# wireless-display-design.net
KiCad netlist of a schematic drawn in EasyEDA Pro
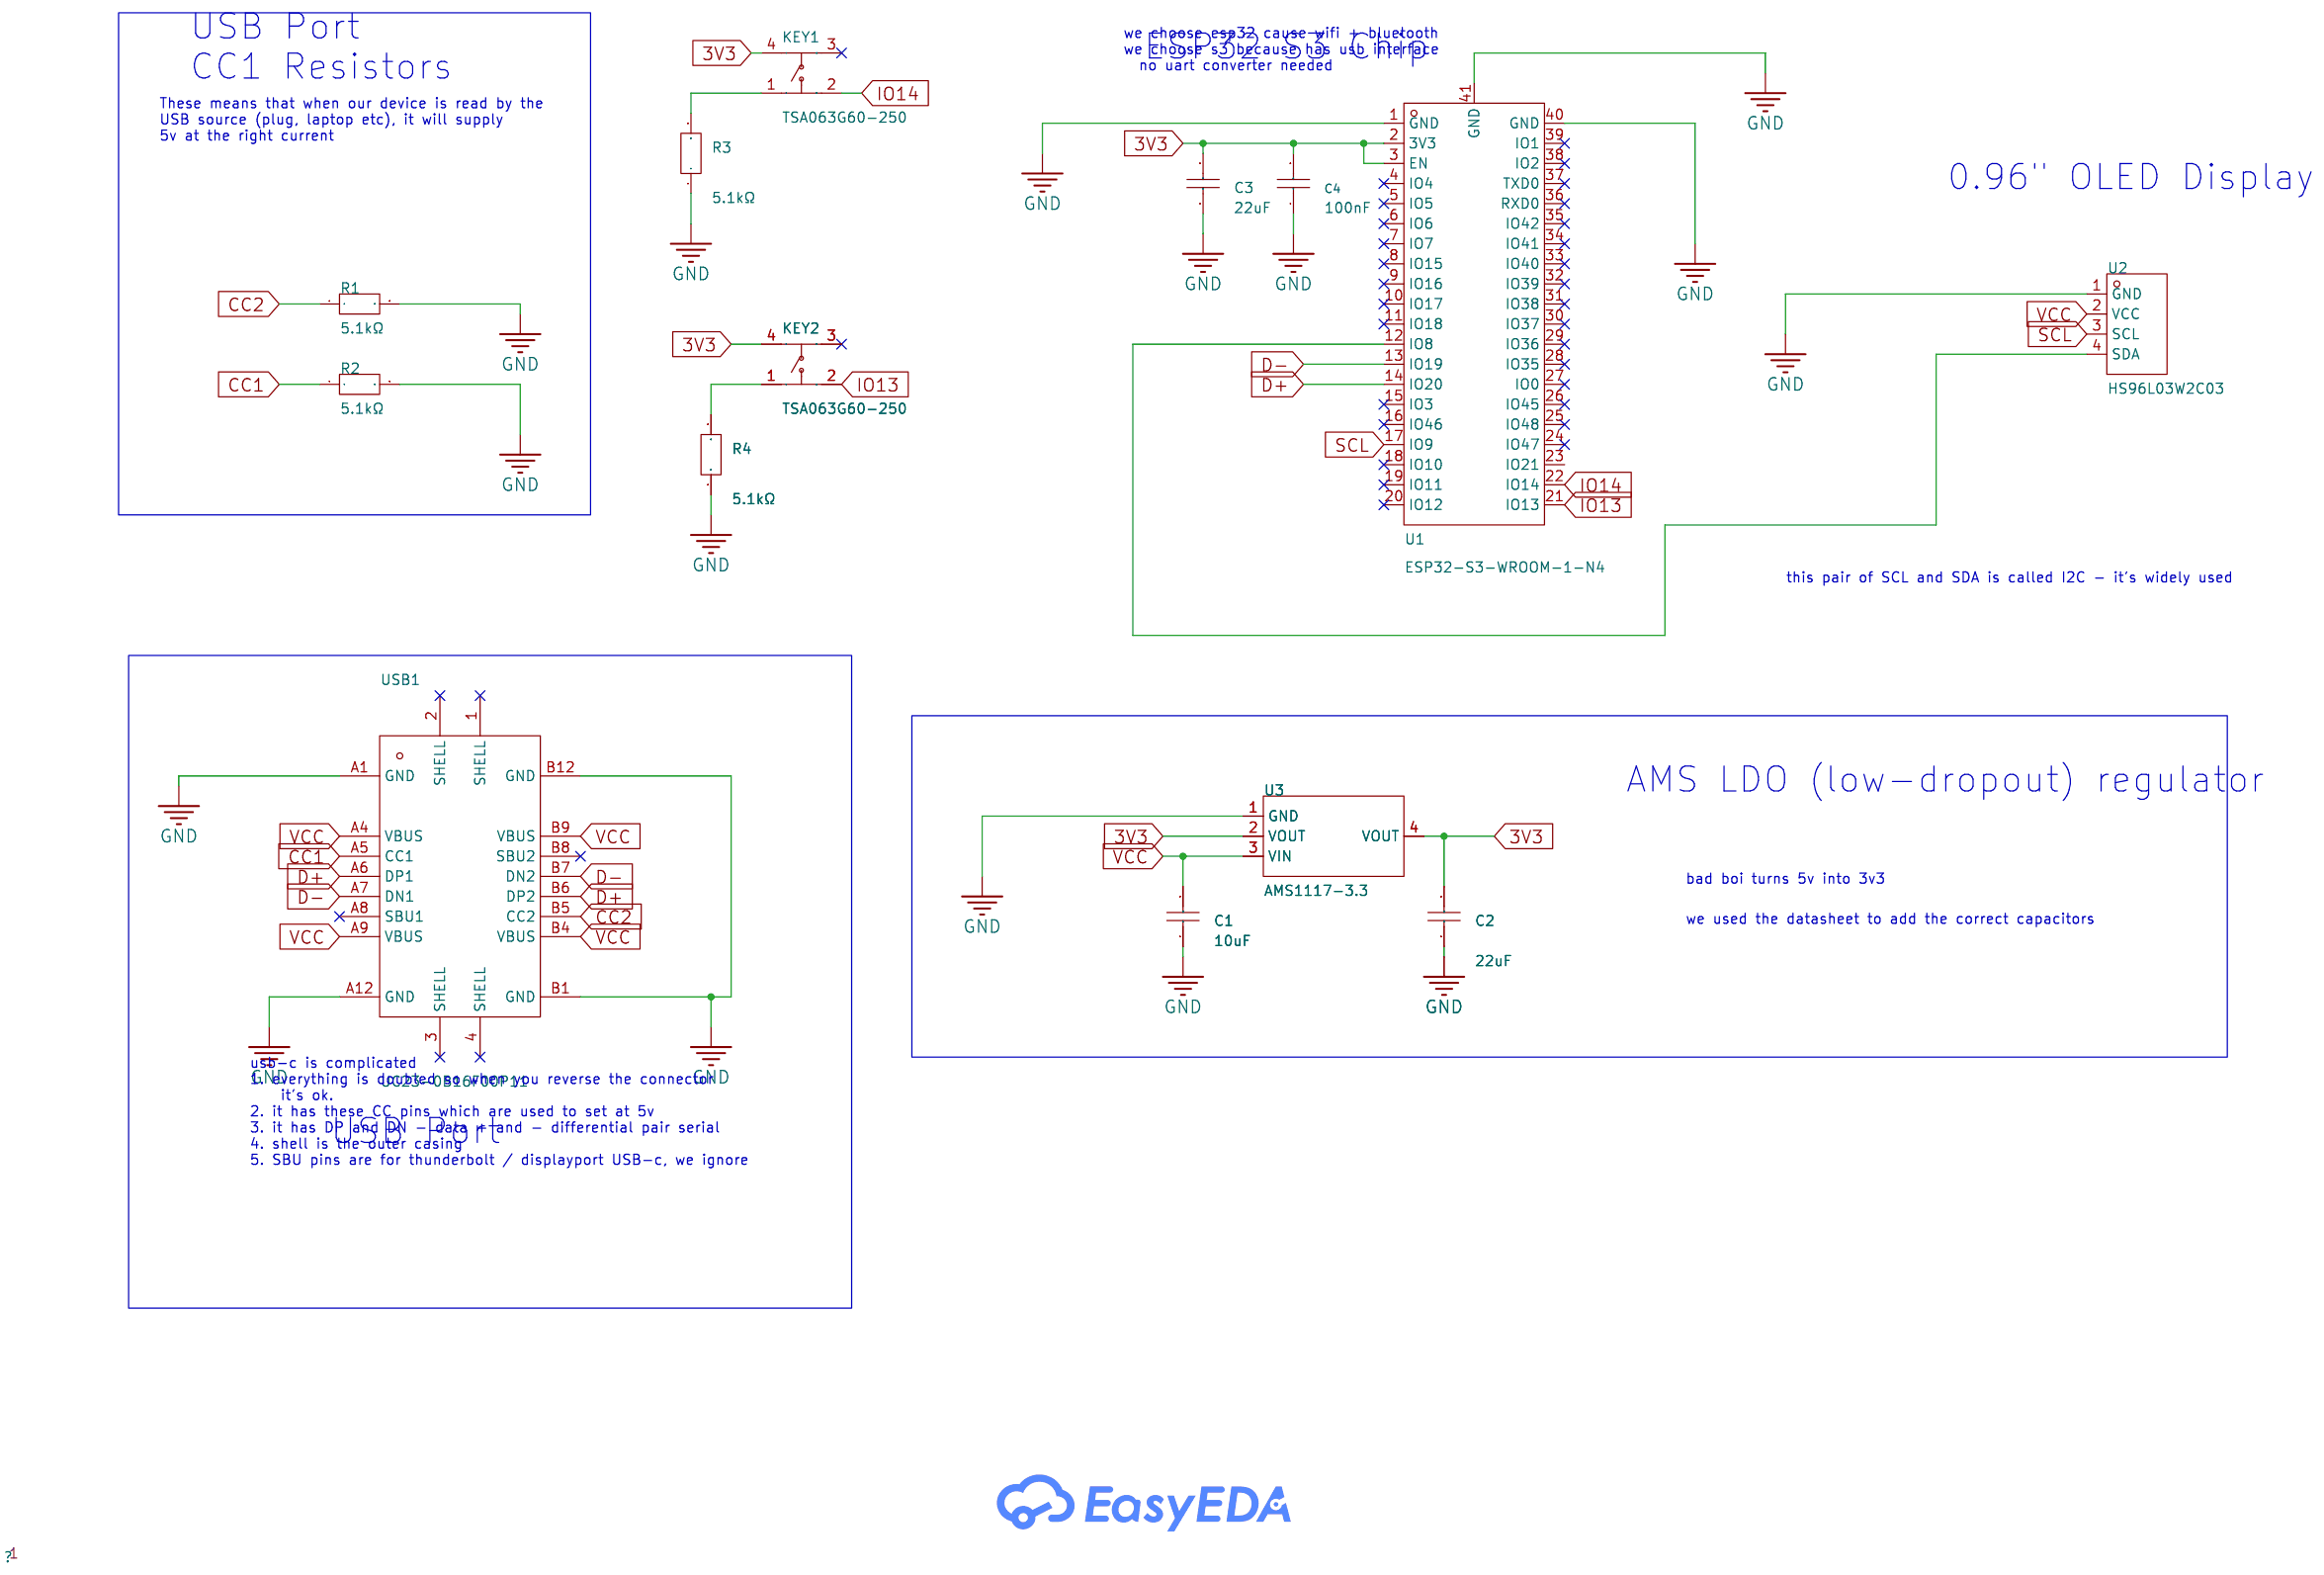
[diagram p0: schematic sheet]

(export (version "E")
  (design (tool "Eeschema 10.0.6"))
  (components
    (comp (ref "C1")
      (value "10uF")
      (footprint "easyedapro:C1206")
      (description "Capacitance:10uF Tolerance:±10% Tolerance:±10% Voltage Rating:50V Temperature Coefficient:X5R")
      (fields
        (field (name "Manufacturer Part") "CL31A106KBHNNNE")
        (field (name "Manufacturer") "SAMSUNG(三星)")
      )
      (libsource (lib "easyedapro") (part "CL31A106KBHNNNE"))
    )
    (comp (ref "C2")
      (value "22uF")
      (footprint "easyedapro:C1206")
      (description "Capacitance:22uF Tolerance:±10% Tolerance:±10% Voltage Rating:25V Temperature Coefficient:X5R")
      (fields
        (field (name "Manufacturer Part") "CL31A226KAHNNNE")
        (field (name "Manufacturer") "SAMSUNG(三星)")
      )
      (libsource (lib "easyedapro") (part "CL31A226KAHNNNE"))
    )
    (comp (ref "C3")
      (value "22uF")
      (footprint "easyedapro:C1206")
      (description "Capacitance:22uF Tolerance:±10% Tolerance:±10% Voltage Rating:25V Temperature Coefficient:X5R")
      (fields
        (field (name "Manufacturer Part") "CL31A226KAHNNNE")
        (field (name "Manufacturer") "SAMSUNG(三星)")
      )
      (libsource (lib "easyedapro") (part "CL31A226KAHNNNE"))
    )
    (comp (ref "C4")
      (value "100nF")
      (footprint "easyedapro:C1206")
      (description "Capacitance:100nF Tolerance:±10% Tolerance:±10% Voltage Rating:50V Temperature Coefficient:X7R")
      (fields
        (field (name "Manufacturer Part") "CL31B104KBCNNNC")
        (field (name "Manufacturer") "SAMSUNG(三星)")
      )
      (libsource (lib "easyedapro") (part "CL31B104KBCNNNC"))
    )
    (comp (ref "KEY1")
      (value "TSA063G60-250")
      (footprint "easyedapro:KEY-SMD_4P-L6.1-W6.1-P4.50-LS9.0")
      (fields (field (name "Manufacturer") "BRIGHT(博瑞泰)"))
      (libsource (lib "easyedapro") (part "TSA063G60-250"))
    )
    (comp (ref "KEY2")
      (value "TSA063G60-250")
      (footprint "easyedapro:KEY-SMD_4P-L6.1-W6.1-P4.50-LS9.0")
      (fields (field (name "Manufacturer") "BRIGHT(博瑞泰)"))
      (libsource (lib "easyedapro") (part "TSA063G60-250"))
    )
    (comp (ref "R1")
      (value "5.1kΩ")
      (footprint "easyedapro:R1206")
      (fields (field (name "Manufacturer Part") "FRC1206J512 TS") (field (name "Manufacturer") "FOJAN(富捷)"))
      (libsource (lib "easyedapro") (part "FRC1206J512 TS"))
    )
    (comp (ref "R2")
      (value "5.1kΩ")
      (footprint "easyedapro:R1206")
      (fields (field (name "Manufacturer Part") "FRC1206J512 TS") (field (name "Manufacturer") "FOJAN(富捷)"))
      (libsource (lib "easyedapro") (part "FRC1206J512 TS"))
    )
    (comp (ref "R3")
      (value "5.1kΩ")
      (footprint "easyedapro:R1206")
      (fields (field (name "Manufacturer Part") "FRC1206J512 TS") (field (name "Manufacturer") "FOJAN(富捷)"))
      (libsource (lib "easyedapro") (part "FRC1206J512 TS"))
    )
    (comp (ref "R4")
      (value "5.1kΩ")
      (footprint "easyedapro:R1206")
      (fields (field (name "Manufacturer Part") "FRC1206J512 TS") (field (name "Manufacturer") "FOJAN(富捷)"))
      (libsource (lib "easyedapro") (part "FRC1206J512 TS"))
    )
    (comp (ref "U1")
      (value "ESP32-S3-WROOM-1-N4")
      (footprint "easyedapro:WIFIM-SMD_ESP32-S3-WROOM-1-N8")
      (fields (field (name "Manufacturer") "ESPRESSIF(乐鑫)"))
      (libsource (lib "easyedapro") (part "ESP32-S3-WROOM-1-N4"))
    )
    (comp (ref "U2")
      (value "HS96L03W2C03")
      (footprint "easyedapro:OLED-TH_L27.8-W27.2-P2.54_C9900033791")
      (fields (field (name "Manufacturer") "HS(汉昇)"))
      (libsource (lib "easyedapro") (part "HS96L03W2C03"))
    )
    (comp (ref "U3")
      (value "AMS1117-3.3")
      (footprint "easyedapro:SOT-223-3_L6.5-W3.4-P2.30-LS7.0-BR")
      (fields (field (name "Manufacturer") "AMS"))
      (libsource (lib "easyedapro") (part "AMS1117-3.3"))
    )
    (comp (ref "USB1")
      (value "UC23-0B16F00P11")
      (footprint "easyedapro:USB-C-TH_UC23-0B16F00P11")
      (fields (field (name "Manufacturer") "BXCONN(宝讯)"))
      (libsource (lib "easyedapro") (part "UC23-0B16F00P11"))
    )
  )
  (nets
    (net (code "1") (name "3V3") (class "Default")
      (node (ref "C2") (pin "2") (pinfunction "2_2") (pintype "input"))
      (node (ref "C3") (pin "2") (pinfunction "2_2") (pintype "input"))
      (node (ref "C4") (pin "2") (pinfunction "2_2") (pintype "input"))
      (node (ref "KEY1") (pin "4") (pinfunction "4_4") (pintype "input"))
      (node (ref "KEY2") (pin "4") (pinfunction "4_4") (pintype "input"))
      (node (ref "U1") (pin "2") (pinfunction "3V3_2") (pintype "unspecified"))
      (node (ref "U1") (pin "3") (pinfunction "EN_3") (pintype "unspecified"))
      (node (ref "U3") (pin "2") (pinfunction "VOUT_2") (pintype "unspecified"))
      (node (ref "U3") (pin "4") (pinfunction "VOUT_4") (pintype "unspecified"))
    )
    (net (code "2") (name "CC1") (class "Default")
      (node (ref "R2") (pin "1") (pinfunction "1_1") (pintype "unspecified"))
      (node (ref "USB1") (pin "A5") (pinfunction "CC1_A5") (pintype "unspecified"))
    )
    (net (code "3") (name "CC2") (class "Default")
      (node (ref "R1") (pin "1") (pinfunction "1_1") (pintype "unspecified"))
      (node (ref "USB1") (pin "B5") (pinfunction "CC2_B5") (pintype "unspecified"))
    )
    (net (code "4") (name "D+") (class "Default")
      (node (ref "U1") (pin "14") (pinfunction "IO20_14") (pintype "unspecified"))
      (node (ref "USB1") (pin "A6") (pinfunction "DP1_A6") (pintype "unspecified"))
      (node (ref "USB1") (pin "B6") (pinfunction "DP2_B6") (pintype "unspecified"))
    )
    (net (code "5") (name "D-") (class "Default")
      (node (ref "U1") (pin "13") (pinfunction "IO19_13") (pintype "unspecified"))
      (node (ref "USB1") (pin "A7") (pinfunction "DN1_A7") (pintype "unspecified"))
      (node (ref "USB1") (pin "B7") (pinfunction "DN2_B7") (pintype "unspecified"))
    )
    (net (code "6") (name "GND") (class "Default")
      (node (ref "C1") (pin "1") (pinfunction "1_1") (pintype "input"))
      (node (ref "C2") (pin "1") (pinfunction "1_1") (pintype "input"))
      (node (ref "C3") (pin "1") (pinfunction "1_1") (pintype "input"))
      (node (ref "C4") (pin "1") (pinfunction "1_1") (pintype "input"))
      (node (ref "R1") (pin "2") (pinfunction "2_2") (pintype "unspecified"))
      (node (ref "R2") (pin "2") (pinfunction "2_2") (pintype "unspecified"))
      (node (ref "R3") (pin "1") (pinfunction "1_1") (pintype "unspecified"))
      (node (ref "R4") (pin "1") (pinfunction "1_1") (pintype "unspecified"))
      (node (ref "U1") (pin "1") (pinfunction "GND_1") (pintype "unspecified"))
      (node (ref "U1") (pin "40") (pinfunction "GND_40") (pintype "unspecified"))
      (node (ref "U1") (pin "41") (pinfunction "GND_41") (pintype "unspecified"))
      (node (ref "U2") (pin "1") (pinfunction "GND_1") (pintype "unspecified"))
      (node (ref "U3") (pin "1") (pinfunction "GND_1") (pintype "unspecified"))
      (node (ref "USB1") (pin "A1") (pinfunction "GND_A1") (pintype "unspecified"))
      (node (ref "USB1") (pin "A12") (pinfunction "GND_A12") (pintype "unspecified"))
      (node (ref "USB1") (pin "B1") (pinfunction "GND_B1") (pintype "unspecified"))
      (node (ref "USB1") (pin "B12") (pinfunction "GND_B12") (pintype "unspecified"))
    )
    (net (code "7") (name "IO13") (class "Default")
      (node (ref "KEY2") (pin "2") (pinfunction "2_2") (pintype "input"))
      (node (ref "U1") (pin "21") (pinfunction "IO13_21") (pintype "unspecified"))
    )
    (net (code "8") (name "IO14") (class "Default")
      (node (ref "KEY1") (pin "2") (pinfunction "2_2") (pintype "input"))
      (node (ref "U1") (pin "22") (pinfunction "IO14_22") (pintype "unspecified"))
    )
    (net (code "9") (name "Net-(KEY1-Pad1)") (class "Default")
      (node (ref "KEY1") (pin "1") (pinfunction "1_1") (pintype "input"))
      (node (ref "R3") (pin "2") (pinfunction "2_2") (pintype "unspecified"))
    )
    (net (code "10") (name "Net-(KEY2-Pad1)") (class "Default")
      (node (ref "KEY2") (pin "1") (pinfunction "1_1") (pintype "input"))
      (node (ref "R4") (pin "2") (pinfunction "2_2") (pintype "unspecified"))
    )
    (net (code "11") (name "Net-(U1-IO8)") (class "Default")
      (node (ref "U1") (pin "12") (pinfunction "IO8_12") (pintype "unspecified"))
      (node (ref "U2") (pin "4") (pinfunction "SDA_4") (pintype "unspecified"))
    )
    (net (code "12") (name "SCL") (class "Default")
      (node (ref "U1") (pin "17") (pinfunction "IO9_17") (pintype "unspecified"))
      (node (ref "U2") (pin "3") (pinfunction "SCL_3") (pintype "unspecified"))
    )
    (net (code "13") (name "VCC") (class "Default")
      (node (ref "C1") (pin "2") (pinfunction "2_2") (pintype "input"))
      (node (ref "U2") (pin "2") (pinfunction "VCC_2") (pintype "unspecified"))
      (node (ref "U3") (pin "3") (pinfunction "VIN_3") (pintype "unspecified"))
      (node (ref "USB1") (pin "A4") (pinfunction "VBUS_A4") (pintype "unspecified"))
      (node (ref "USB1") (pin "A9") (pinfunction "VBUS_A9") (pintype "unspecified"))
      (node (ref "USB1") (pin "B4") (pinfunction "VBUS_B4") (pintype "unspecified"))
      (node (ref "USB1") (pin "B9") (pinfunction "VBUS_B9") (pintype "unspecified"))
    )
    (net (code "14") (name "unconnected-(KEY1-Pad3)") (class "Default")
      (node (ref "KEY1") (pin "3") (pinfunction "3_3") (pintype "input+no_connect"))
    )
    (net (code "15") (name "unconnected-(KEY2-Pad3)") (class "Default")
      (node (ref "KEY2") (pin "3") (pinfunction "3_3") (pintype "input+no_connect"))
    )
    (net (code "16") (name "unconnected-(U1-IO0-Pad27)") (class "Default")
      (node (ref "U1") (pin "27") (pinfunction "IO0_27") (pintype "unspecified+no_connect"))
    )
    (net (code "17") (name "unconnected-(U1-IO1-Pad39)") (class "Default")
      (node (ref "U1") (pin "39") (pinfunction "IO1_39") (pintype "unspecified+no_connect"))
    )
    (net (code "18") (name "unconnected-(U1-IO2-Pad38)") (class "Default")
      (node (ref "U1") (pin "38") (pinfunction "IO2_38") (pintype "unspecified+no_connect"))
    )
    (net (code "19") (name "unconnected-(U1-IO3-Pad15)") (class "Default")
      (node (ref "U1") (pin "15") (pinfunction "IO3_15") (pintype "unspecified+no_connect"))
    )
    (net (code "20") (name "unconnected-(U1-IO4-Pad4)") (class "Default")
      (node (ref "U1") (pin "4") (pinfunction "IO4_4") (pintype "unspecified+no_connect"))
    )
    (net (code "21") (name "unconnected-(U1-IO5-Pad5)") (class "Default")
      (node (ref "U1") (pin "5") (pinfunction "IO5_5") (pintype "unspecified+no_connect"))
    )
    (net (code "22") (name "unconnected-(U1-IO6-Pad6)") (class "Default")
      (node (ref "U1") (pin "6") (pinfunction "IO6_6") (pintype "unspecified+no_connect"))
    )
    (net (code "23") (name "unconnected-(U1-IO7-Pad7)") (class "Default")
      (node (ref "U1") (pin "7") (pinfunction "IO7_7") (pintype "unspecified+no_connect"))
    )
    (net (code "24") (name "unconnected-(U1-IO10-Pad18)") (class "Default")
      (node (ref "U1") (pin "18") (pinfunction "IO10_18") (pintype "unspecified+no_connect"))
    )
    (net (code "25") (name "unconnected-(U1-IO11-Pad19)") (class "Default")
      (node (ref "U1") (pin "19") (pinfunction "IO11_19") (pintype "unspecified+no_connect"))
    )
    (net (code "26") (name "unconnected-(U1-IO12-Pad20)") (class "Default")
      (node (ref "U1") (pin "20") (pinfunction "IO12_20") (pintype "unspecified+no_connect"))
    )
    (net (code "27") (name "unconnected-(U1-IO15-Pad8)") (class "Default")
      (node (ref "U1") (pin "8") (pinfunction "IO15_8") (pintype "unspecified+no_connect"))
    )
    (net (code "28") (name "unconnected-(U1-IO16-Pad9)") (class "Default")
      (node (ref "U1") (pin "9") (pinfunction "IO16_9") (pintype "unspecified+no_connect"))
    )
    (net (code "29") (name "unconnected-(U1-IO17-Pad10)") (class "Default")
      (node (ref "U1") (pin "10") (pinfunction "IO17_10") (pintype "unspecified+no_connect"))
    )
    (net (code "30") (name "unconnected-(U1-IO18-Pad11)") (class "Default")
      (node (ref "U1") (pin "11") (pinfunction "IO18_11") (pintype "unspecified+no_connect"))
    )
    (net (code "31") (name "unconnected-(U1-IO21-Pad23)") (class "Default")
      (node (ref "U1") (pin "23") (pinfunction "IO21_23") (pintype "unspecified"))
    )
    (net (code "32") (name "unconnected-(U1-IO35-Pad28)") (class "Default")
      (node (ref "U1") (pin "28") (pinfunction "IO35_28") (pintype "unspecified+no_connect"))
    )
    (net (code "33") (name "unconnected-(U1-IO36-Pad29)") (class "Default")
      (node (ref "U1") (pin "29") (pinfunction "IO36_29") (pintype "unspecified+no_connect"))
    )
    (net (code "34") (name "unconnected-(U1-IO37-Pad30)") (class "Default")
      (node (ref "U1") (pin "30") (pinfunction "IO37_30") (pintype "unspecified+no_connect"))
    )
    (net (code "35") (name "unconnected-(U1-IO38-Pad31)") (class "Default")
      (node (ref "U1") (pin "31") (pinfunction "IO38_31") (pintype "unspecified+no_connect"))
    )
    (net (code "36") (name "unconnected-(U1-IO39-Pad32)") (class "Default")
      (node (ref "U1") (pin "32") (pinfunction "IO39_32") (pintype "unspecified+no_connect"))
    )
    (net (code "37") (name "unconnected-(U1-IO40-Pad33)") (class "Default")
      (node (ref "U1") (pin "33") (pinfunction "IO40_33") (pintype "unspecified+no_connect"))
    )
    (net (code "38") (name "unconnected-(U1-IO41-Pad34)") (class "Default")
      (node (ref "U1") (pin "34") (pinfunction "IO41_34") (pintype "unspecified+no_connect"))
    )
    (net (code "39") (name "unconnected-(U1-IO42-Pad35)") (class "Default")
      (node (ref "U1") (pin "35") (pinfunction "IO42_35") (pintype "unspecified+no_connect"))
    )
    (net (code "40") (name "unconnected-(U1-IO45-Pad26)") (class "Default")
      (node (ref "U1") (pin "26") (pinfunction "IO45_26") (pintype "unspecified+no_connect"))
    )
    (net (code "41") (name "unconnected-(U1-IO46-Pad16)") (class "Default")
      (node (ref "U1") (pin "16") (pinfunction "IO46_16") (pintype "unspecified+no_connect"))
    )
    (net (code "42") (name "unconnected-(U1-IO47-Pad24)") (class "Default")
      (node (ref "U1") (pin "24") (pinfunction "IO47_24") (pintype "unspecified+no_connect"))
    )
    (net (code "43") (name "unconnected-(U1-IO48-Pad25)") (class "Default")
      (node (ref "U1") (pin "25") (pinfunction "IO48_25") (pintype "unspecified+no_connect"))
    )
    (net (code "44") (name "unconnected-(U1-RXD0-Pad36)") (class "Default")
      (node (ref "U1") (pin "36") (pinfunction "RXD0_36") (pintype "unspecified+no_connect"))
    )
    (net (code "45") (name "unconnected-(U1-TXD0-Pad37)") (class "Default")
      (node (ref "U1") (pin "37") (pinfunction "TXD0_37") (pintype "unspecified+no_connect"))
    )
    (net (code "46") (name "unconnected-(USB1-SBU1-PadA8)") (class "Default")
      (node (ref "USB1") (pin "A8") (pinfunction "SBU1_A8") (pintype "unspecified+no_connect"))
    )
    (net (code "47") (name "unconnected-(USB1-SBU2-PadB8)") (class "Default")
      (node (ref "USB1") (pin "B8") (pinfunction "SBU2_B8") (pintype "unspecified+no_connect"))
    )
    (net (code "48") (name "unconnected-(USB1-SHELL-Pad1)") (class "Default")
      (node (ref "USB1") (pin "1") (pinfunction "SHELL_1") (pintype "unspecified+no_connect"))
    )
    (net (code "49") (name "unconnected-(USB1-SHELL-Pad2)") (class "Default")
      (node (ref "USB1") (pin "2") (pinfunction "SHELL_2") (pintype "unspecified+no_connect"))
    )
    (net (code "50") (name "unconnected-(USB1-SHELL-Pad3)") (class "Default")
      (node (ref "USB1") (pin "3") (pinfunction "SHELL_3") (pintype "unspecified+no_connect"))
    )
    (net (code "51") (name "unconnected-(USB1-SHELL-Pad4)") (class "Default")
      (node (ref "USB1") (pin "4") (pinfunction "SHELL_4") (pintype "unspecified+no_connect"))
    )
  )
)
